# PF3_MS.net
KiCad netlist of a schematic drawn in Altium Designer
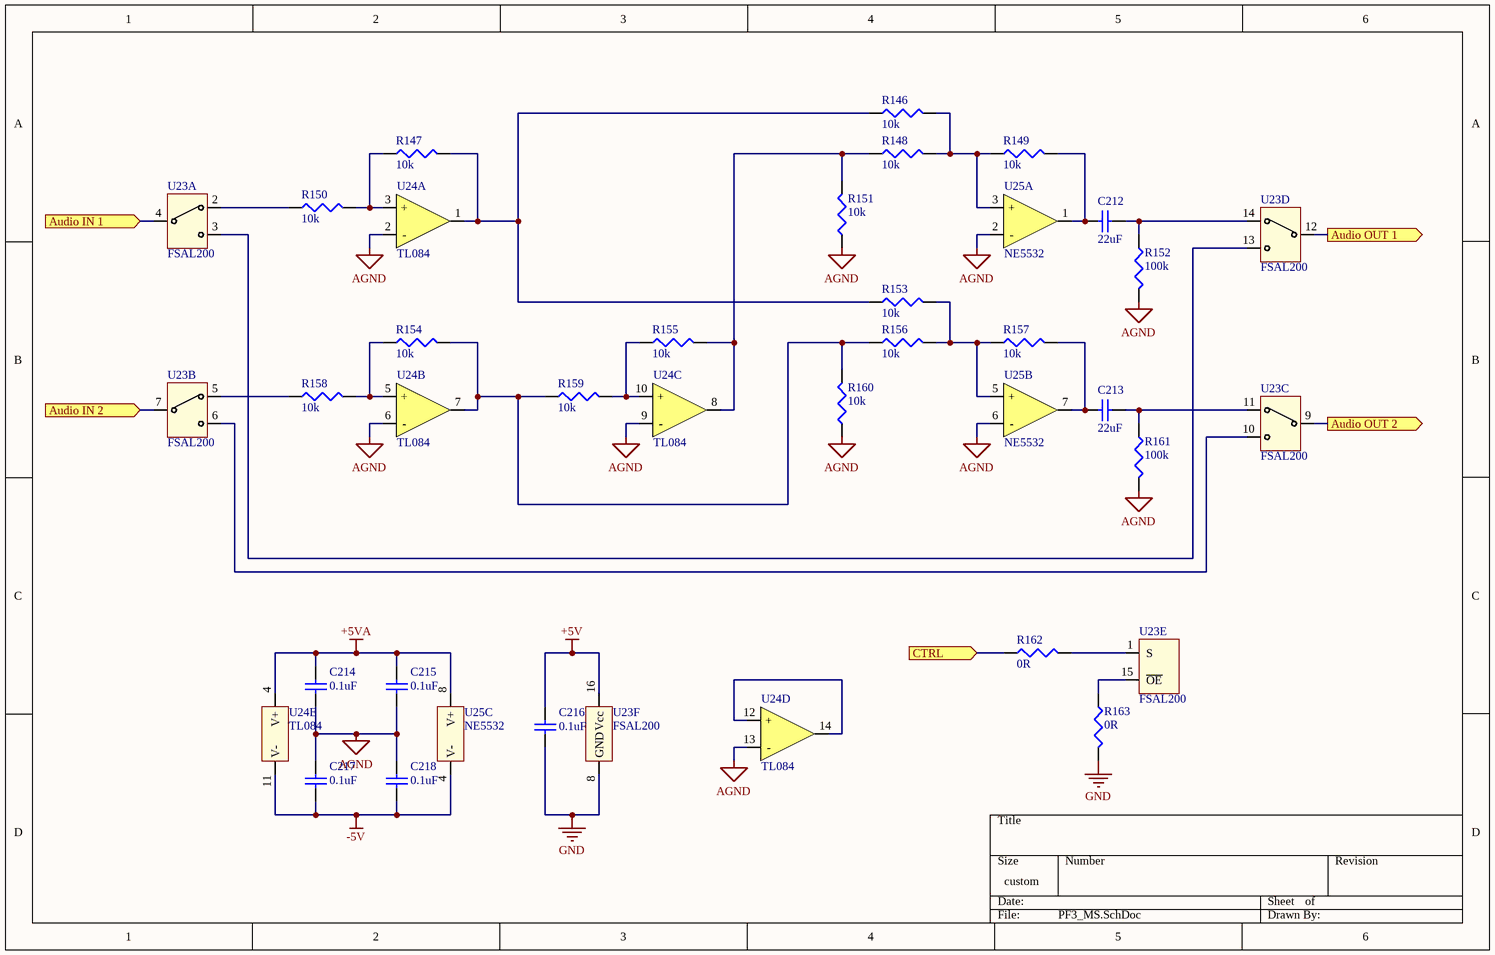
[diagram p0: PF3_MS.SchDoc]

(export (version "E")
  (design (tool "Eeschema 10.0.6"))
  (components
    (comp (ref "C212")
      (value "22uF")
      (footprint "CAPC1608X08")
      (description "Capacitor (Semiconductor SIM Model)")
      (libsource (lib "Michel") (part "Cap Semi"))
    )
    (comp (ref "C213")
      (value "22uF")
      (footprint "CAPC1608X08")
      (description "Capacitor (Semiconductor SIM Model)")
      (libsource (lib "Michel") (part "Cap Semi"))
    )
    (comp (ref "C214")
      (value "0.1uF")
      (footprint "CAPC1608X08")
      (description "Capacitor (Semiconductor SIM Model)")
      (libsource (lib "Michel") (part "Cap Semi"))
    )
    (comp (ref "C215")
      (value "0.1uF")
      (footprint "CAPC1608X08")
      (description "Capacitor (Semiconductor SIM Model)")
      (libsource (lib "Michel") (part "Cap Semi"))
    )
    (comp (ref "C216")
      (value "0.1uF")
      (footprint "CAPC1608X08")
      (description "Capacitor (Semiconductor SIM Model)")
      (libsource (lib "Michel") (part "Cap Semi"))
    )
    (comp (ref "C217")
      (value "0.1uF")
      (footprint "CAPC1608X08")
      (description "Capacitor (Semiconductor SIM Model)")
      (libsource (lib "Michel") (part "Cap Semi"))
    )
    (comp (ref "C218")
      (value "0.1uF")
      (footprint "CAPC1608X08")
      (description "Capacitor (Semiconductor SIM Model)")
      (libsource (lib "Michel") (part "Cap Semi"))
    )
    (comp (ref "R146")
      (value "10k")
      (footprint "RESC1608X05")
      (description "Resistor")
      (libsource (lib "Michel") (part "Res3"))
    )
    (comp (ref "R147")
      (value "10k")
      (footprint "RESC1608X05")
      (description "Resistor")
      (libsource (lib "Michel") (part "Res3"))
    )
    (comp (ref "R148")
      (value "10k")
      (footprint "RESC1608X05")
      (description "Resistor")
      (libsource (lib "Michel") (part "Res3"))
    )
    (comp (ref "R149")
      (value "10k")
      (footprint "RESC1608X05")
      (description "Resistor")
      (libsource (lib "Michel") (part "Res3"))
    )
    (comp (ref "R150")
      (value "10k")
      (footprint "RESC1608X05")
      (description "Resistor")
      (libsource (lib "Michel") (part "Res3"))
    )
    (comp (ref "R151")
      (value "10k")
      (footprint "RESC1608X05")
      (description "Resistor")
      (libsource (lib "Michel") (part "Res3"))
    )
    (comp (ref "R152")
      (value "100k")
      (footprint "RESC1608X05")
      (description "Resistor")
      (libsource (lib "Michel") (part "Res3"))
    )
    (comp (ref "R153")
      (value "10k")
      (footprint "RESC1608X05")
      (description "Resistor")
      (libsource (lib "Michel") (part "Res3"))
    )
    (comp (ref "R154")
      (value "10k")
      (footprint "RESC1608X05")
      (description "Resistor")
      (libsource (lib "Michel") (part "Res3"))
    )
    (comp (ref "R155")
      (value "10k")
      (footprint "RESC1608X05")
      (description "Resistor")
      (libsource (lib "Michel") (part "Res3"))
    )
    (comp (ref "R156")
      (value "10k")
      (footprint "RESC1608X05")
      (description "Resistor")
      (libsource (lib "Michel") (part "Res3"))
    )
    (comp (ref "R157")
      (value "10k")
      (footprint "RESC1608X05")
      (description "Resistor")
      (libsource (lib "Michel") (part "Res3"))
    )
    (comp (ref "R158")
      (value "10k")
      (footprint "RESC1608X05")
      (description "Resistor")
      (libsource (lib "Michel") (part "Res3"))
    )
    (comp (ref "R159")
      (value "10k")
      (footprint "RESC1608X05")
      (description "Resistor")
      (libsource (lib "Michel") (part "Res3"))
    )
    (comp (ref "R160")
      (value "10k")
      (footprint "RESC1608X05")
      (description "Resistor")
      (libsource (lib "Michel") (part "Res3"))
    )
    (comp (ref "R161")
      (value "100k")
      (footprint "RESC1608X05")
      (description "Resistor")
      (libsource (lib "Michel") (part "Res3"))
    )
    (comp (ref "R162")
      (value "0R")
      (footprint "RESC1608X05")
      (description "Resistor")
      (libsource (lib "Michel") (part "Res3"))
    )
    (comp (ref "R163")
      (value "0R")
      (footprint "RESC1608X05")
      (description "Resistor")
      (libsource (lib "Michel") (part "Res3"))
    )
    (comp (ref "U23")
      (value "FSAL200")
      (footprint "TSOP65P730X110-16N")
      (description "Quad 2:1 Multiplexer")
      (libsource (lib "Michel") (part "FSAL200"))
    )
    (comp (ref "U24")
      (value "TL084")
      (footprint "D14-M")
      (description "Quad Audio OpAmp")
      (libsource (lib "Michel") (part "TL084"))
    )
    (comp (ref "U25")
      (value "NE5532")
      (footprint "D8-M")
      (description "Dual Audio OpAmp")
      (libsource (lib "Michel") (part "NE5532"))
    )
  )
  (nets
    (net (code "1") (name "+5V") (class "Default")
      (node (ref "C216") (pin "1") (pinfunction "1_1") (pintype "passive"))
      (node (ref "U23") (pin "16") (pinfunction "Vcc_16") (pintype "power_in"))
    )
    (net (code "2") (name "+5VA") (class "Default")
      (node (ref "C214") (pin "1") (pinfunction "1_1") (pintype "passive"))
      (node (ref "C215") (pin "1") (pinfunction "1_1") (pintype "passive"))
      (node (ref "U24") (pin "4") (pinfunction "V+_4") (pintype "power_in"))
      (node (ref "U25") (pin "8") (pinfunction "V+_8") (pintype "power_in"))
    )
    (net (code "3") (name "-5V") (class "Default")
      (node (ref "C217") (pin "2") (pinfunction "2_2") (pintype "passive"))
      (node (ref "C218") (pin "2") (pinfunction "2_2") (pintype "passive"))
      (node (ref "U24") (pin "11") (pinfunction "V-_11") (pintype "power_in"))
      (node (ref "U25") (pin "4") (pinfunction "V-_4") (pintype "power_in"))
    )
    (net (code "4") (name "/Audio IN 1") (class "Default")
      (node (ref "U23") (pin "4") (pinfunction "A_4") (pintype "passive"))
    )
    (net (code "5") (name "/Audio IN 2") (class "Default")
      (node (ref "U23") (pin "7") (pinfunction "A_7") (pintype "passive"))
    )
    (net (code "6") (name "/Audio OUT 1") (class "Default")
      (node (ref "U23") (pin "12") (pinfunction "A_12") (pintype "passive"))
    )
    (net (code "7") (name "/Audio OUT 2") (class "Default")
      (node (ref "U23") (pin "9") (pinfunction "A_9") (pintype "passive"))
    )
    (net (code "8") (name "/CTRL") (class "Default")
      (node (ref "R162") (pin "1") (pinfunction "1_1") (pintype "passive"))
    )
    (net (code "9") (name "AGND") (class "Default")
      (node (ref "C214") (pin "2") (pinfunction "2_2") (pintype "passive"))
      (node (ref "C215") (pin "2") (pinfunction "2_2") (pintype "passive"))
      (node (ref "C217") (pin "1") (pinfunction "1_1") (pintype "passive"))
      (node (ref "C218") (pin "1") (pinfunction "1_1") (pintype "passive"))
      (node (ref "R151") (pin "1") (pinfunction "1_1") (pintype "passive"))
      (node (ref "R152") (pin "2") (pinfunction "2_2") (pintype "passive"))
      (node (ref "R160") (pin "1") (pinfunction "1_1") (pintype "passive"))
      (node (ref "R161") (pin "2") (pinfunction "2_2") (pintype "passive"))
      (node (ref "U24") (pin "13") (pinfunction "-_13") (pintype "passive"))
      (node (ref "U24") (pin "2") (pinfunction "-_2") (pintype "passive"))
      (node (ref "U24") (pin "6") (pinfunction "-_6") (pintype "passive"))
      (node (ref "U24") (pin "9") (pinfunction "-_9") (pintype "passive"))
      (node (ref "U25") (pin "2") (pinfunction "-_2") (pintype "passive"))
      (node (ref "U25") (pin "6") (pinfunction "-_6") (pintype "passive"))
    )
    (net (code "10") (name "GND") (class "Default")
      (node (ref "C216") (pin "2") (pinfunction "2_2") (pintype "passive"))
      (node (ref "R163") (pin "2") (pinfunction "2_2") (pintype "passive"))
      (node (ref "U23") (pin "8") (pinfunction "GND_8") (pintype "power_in"))
    )
    (net (code "11") (name "Net-(U23A-B1)") (class "Default")
      (node (ref "R150") (pin "1") (pinfunction "1_1") (pintype "passive"))
      (node (ref "U23") (pin "2") (pinfunction "B1_2") (pintype "passive"))
    )
    (net (code "12") (name "Net-(U23A-B2)") (class "Default")
      (node (ref "U23") (pin "13") (pinfunction "B2_13") (pintype "passive"))
      (node (ref "U23") (pin "3") (pinfunction "B2_3") (pintype "passive"))
    )
    (net (code "13") (name "Net-(U23B-B1)") (class "Default")
      (node (ref "R158") (pin "1") (pinfunction "1_1") (pintype "passive"))
      (node (ref "U23") (pin "5") (pinfunction "B1_5") (pintype "passive"))
    )
    (net (code "14") (name "Net-(U23B-B2)") (class "Default")
      (node (ref "U23") (pin "10") (pinfunction "B2_10") (pintype "passive"))
      (node (ref "U23") (pin "6") (pinfunction "B2_6") (pintype "passive"))
    )
    (net (code "15") (name "Net-(U23C-B1)") (class "Default")
      (node (ref "C213") (pin "1") (pinfunction "1_1") (pintype "passive"))
      (node (ref "R161") (pin "1") (pinfunction "1_1") (pintype "passive"))
      (node (ref "U23") (pin "11") (pinfunction "B1_11") (pintype "passive"))
    )
    (net (code "16") (name "Net-(U23D-B1)") (class "Default")
      (node (ref "C212") (pin "1") (pinfunction "1_1") (pintype "passive"))
      (node (ref "R152") (pin "1") (pinfunction "1_1") (pintype "passive"))
      (node (ref "U23") (pin "14") (pinfunction "B1_14") (pintype "passive"))
    )
    (net (code "17") (name "Net-(U23E-S)") (class "Default")
      (node (ref "R162") (pin "2") (pinfunction "2_2") (pintype "passive"))
      (node (ref "U23") (pin "1") (pinfunction "S_1") (pintype "passive"))
    )
    (net (code "18") (name "Net-(U23E-~{OE})") (class "Default")
      (node (ref "R163") (pin "1") (pinfunction "1_1") (pintype "passive"))
      (node (ref "U23") (pin "15") (pinfunction "~{OE}_15") (pintype "passive"))
    )
    (net (code "19") (name "Net-(U24A-+)") (class "Default")
      (node (ref "R147") (pin "1") (pinfunction "1_1") (pintype "passive"))
      (node (ref "R150") (pin "2") (pinfunction "2_2") (pintype "passive"))
      (node (ref "U24") (pin "3") (pinfunction "+_3") (pintype "passive"))
    )
    (net (code "20") (name "Net-(U24A-OUT)") (class "Default")
      (node (ref "R146") (pin "1") (pinfunction "1_1") (pintype "passive"))
      (node (ref "R147") (pin "2") (pinfunction "2_2") (pintype "passive"))
      (node (ref "R153") (pin "1") (pinfunction "1_1") (pintype "passive"))
      (node (ref "U24") (pin "1") (pinfunction "OUT_1") (pintype "passive"))
    )
    (net (code "21") (name "Net-(U24B-+)") (class "Default")
      (node (ref "R154") (pin "1") (pinfunction "1_1") (pintype "passive"))
      (node (ref "R158") (pin "2") (pinfunction "2_2") (pintype "passive"))
      (node (ref "U24") (pin "5") (pinfunction "+_5") (pintype "passive"))
    )
    (net (code "22") (name "Net-(U24B-OUT)") (class "Default")
      (node (ref "R154") (pin "2") (pinfunction "2_2") (pintype "passive"))
      (node (ref "R156") (pin "1") (pinfunction "1_1") (pintype "passive"))
      (node (ref "R159") (pin "1") (pinfunction "1_1") (pintype "passive"))
      (node (ref "R160") (pin "2") (pinfunction "2_2") (pintype "passive"))
      (node (ref "U24") (pin "7") (pinfunction "OUT_7") (pintype "passive"))
    )
    (net (code "23") (name "Net-(U24C-+)") (class "Default")
      (node (ref "R155") (pin "1") (pinfunction "1_1") (pintype "passive"))
      (node (ref "R159") (pin "2") (pinfunction "2_2") (pintype "passive"))
      (node (ref "U24") (pin "10") (pinfunction "+_10") (pintype "passive"))
    )
    (net (code "24") (name "Net-(U24C-OUT)") (class "Default")
      (node (ref "R148") (pin "1") (pinfunction "1_1") (pintype "passive"))
      (node (ref "R151") (pin "2") (pinfunction "2_2") (pintype "passive"))
      (node (ref "R155") (pin "2") (pinfunction "2_2") (pintype "passive"))
      (node (ref "U24") (pin "8") (pinfunction "OUT_8") (pintype "passive"))
    )
    (net (code "25") (name "Net-(U24D-+)") (class "Default")
      (node (ref "U24") (pin "12") (pinfunction "+_12") (pintype "passive"))
      (node (ref "U24") (pin "14") (pinfunction "OUT_14") (pintype "passive"))
    )
    (net (code "26") (name "Net-(U25A-+)") (class "Default")
      (node (ref "R146") (pin "2") (pinfunction "2_2") (pintype "passive"))
      (node (ref "R148") (pin "2") (pinfunction "2_2") (pintype "passive"))
      (node (ref "R149") (pin "1") (pinfunction "1_1") (pintype "passive"))
      (node (ref "U25") (pin "3") (pinfunction "+_3") (pintype "passive"))
    )
    (net (code "27") (name "Net-(U25A-OUT)") (class "Default")
      (node (ref "C212") (pin "2") (pinfunction "2_2") (pintype "passive"))
      (node (ref "R149") (pin "2") (pinfunction "2_2") (pintype "passive"))
      (node (ref "U25") (pin "1") (pinfunction "OUT_1") (pintype "passive"))
    )
    (net (code "28") (name "Net-(U25B-+)") (class "Default")
      (node (ref "R153") (pin "2") (pinfunction "2_2") (pintype "passive"))
      (node (ref "R156") (pin "2") (pinfunction "2_2") (pintype "passive"))
      (node (ref "R157") (pin "1") (pinfunction "1_1") (pintype "passive"))
      (node (ref "U25") (pin "5") (pinfunction "+_5") (pintype "passive"))
    )
    (net (code "29") (name "Net-(U25B-OUT)") (class "Default")
      (node (ref "C213") (pin "2") (pinfunction "2_2") (pintype "passive"))
      (node (ref "R157") (pin "2") (pinfunction "2_2") (pintype "passive"))
      (node (ref "U25") (pin "7") (pinfunction "OUT_7") (pintype "passive"))
    )
  )
)
